# defender.net
KiCad netlist of a schematic drawn in EAGLE
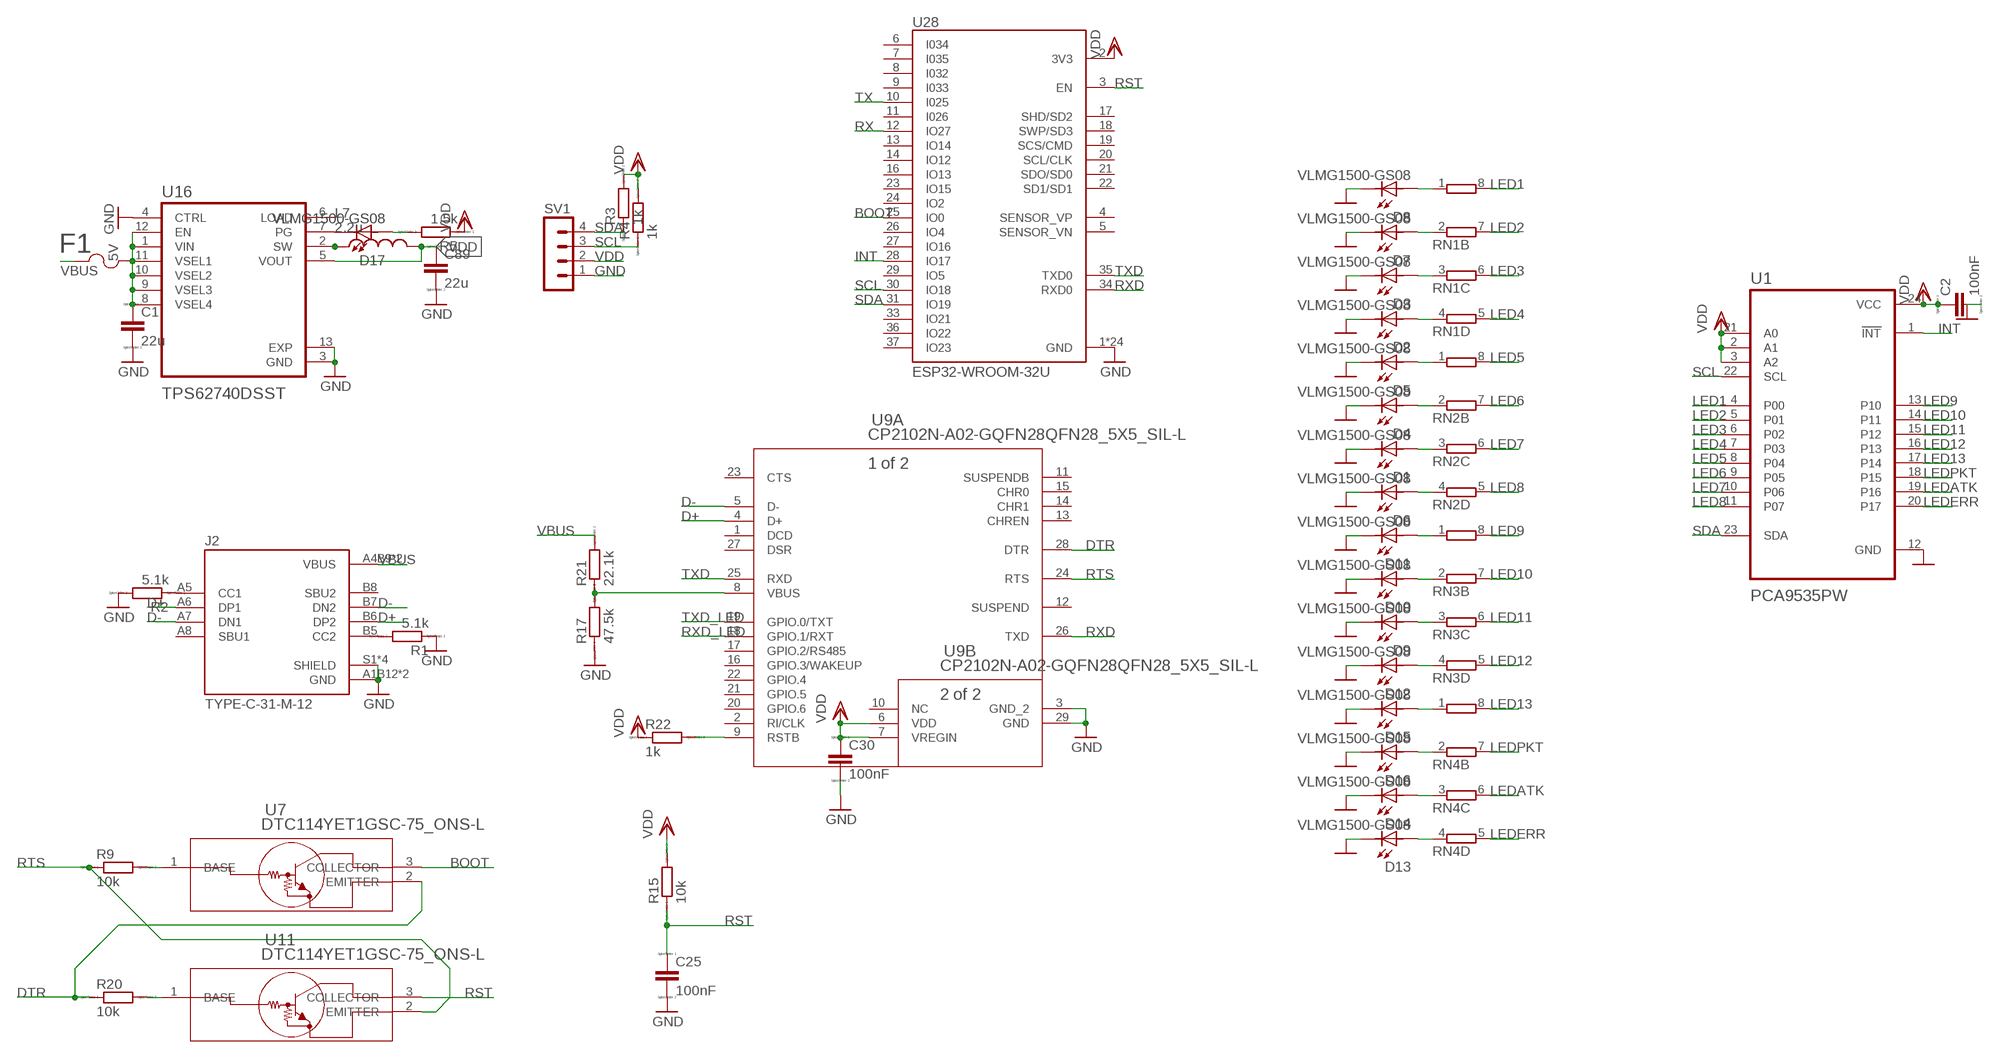
[diagram p0: schematic, sheet 1]

(export (version "E")
  (design (tool "Eeschema 10.0.6"))
  (components
    (comp (ref "C1")
      (value "22u")
      (footprint "eagle-import:C0603R")
      (libsource (lib "eagle-import") (part "CC0603R"))
    )
    (comp (ref "C2")
      (value "100nF")
      (footprint "eagle-import:C0402")
      (libsource (lib "eagle-import") (part "CC0402"))
    )
    (comp (ref "C25")
      (value "100nF")
      (footprint "eagle-import:C0402")
      (libsource (lib "eagle-import") (part "CC0402"))
    )
    (comp (ref "C30")
      (value "100nF")
      (footprint "eagle-import:C0402")
      (libsource (lib "eagle-import") (part "CC0402"))
    )
    (comp (ref "C89")
      (value "22u")
      (footprint "eagle-import:C0603R")
      (libsource (lib "eagle-import") (part "CC0603R"))
    )
    (comp (ref "D1")
      (value "VLMG1500-GS08")
      (footprint "eagle-import:LEDC1005X35N")
      (fields (field (name "MF") "Vishay"))
      (libsource (lib "eagle-import") (part "VLMG1500-GS08"))
    )
    (comp (ref "D2")
      (value "VLMG1500-GS08")
      (footprint "eagle-import:LEDC1005X35N")
      (fields (field (name "MF") "Vishay"))
      (libsource (lib "eagle-import") (part "VLMG1500-GS08"))
    )
    (comp (ref "D3")
      (value "VLMG1500-GS08")
      (footprint "eagle-import:LEDC1005X35N")
      (fields (field (name "MF") "Vishay"))
      (libsource (lib "eagle-import") (part "VLMG1500-GS08"))
    )
    (comp (ref "D4")
      (value "VLMG1500-GS08")
      (footprint "eagle-import:LEDC1005X35N")
      (fields (field (name "MF") "Vishay"))
      (libsource (lib "eagle-import") (part "VLMG1500-GS08"))
    )
    (comp (ref "D5")
      (value "VLMG1500-GS08")
      (footprint "eagle-import:LEDC1005X35N")
      (fields (field (name "MF") "Vishay"))
      (libsource (lib "eagle-import") (part "VLMG1500-GS08"))
    )
    (comp (ref "D6")
      (value "VLMG1500-GS08")
      (footprint "eagle-import:LEDC1005X35N")
      (fields (field (name "MF") "Vishay"))
      (libsource (lib "eagle-import") (part "VLMG1500-GS08"))
    )
    (comp (ref "D7")
      (value "VLMG1500-GS08")
      (footprint "eagle-import:LEDC1005X35N")
      (fields (field (name "MF") "Vishay"))
      (libsource (lib "eagle-import") (part "VLMG1500-GS08"))
    )
    (comp (ref "D8")
      (value "VLMG1500-GS08")
      (footprint "eagle-import:LEDC1005X35N")
      (fields (field (name "MF") "Vishay"))
      (libsource (lib "eagle-import") (part "VLMG1500-GS08"))
    )
    (comp (ref "D9")
      (value "VLMG1500-GS08")
      (footprint "eagle-import:LEDC1005X35N")
      (fields (field (name "MF") "Vishay"))
      (libsource (lib "eagle-import") (part "VLMG1500-GS08"))
    )
    (comp (ref "D10")
      (value "VLMG1500-GS08")
      (footprint "eagle-import:LEDC1005X35N")
      (fields (field (name "MF") "Vishay"))
      (libsource (lib "eagle-import") (part "VLMG1500-GS08"))
    )
    (comp (ref "D11")
      (value "VLMG1500-GS08")
      (footprint "eagle-import:LEDC1005X35N")
      (fields (field (name "MF") "Vishay"))
      (libsource (lib "eagle-import") (part "VLMG1500-GS08"))
    )
    (comp (ref "D12")
      (value "VLMG1500-GS08")
      (footprint "eagle-import:LEDC1005X35N")
      (fields (field (name "MF") "Vishay"))
      (libsource (lib "eagle-import") (part "VLMG1500-GS08"))
    )
    (comp (ref "D13")
      (value "VLMG1500-GS08")
      (footprint "eagle-import:LEDC1005X35N")
      (fields (field (name "MF") "Vishay"))
      (libsource (lib "eagle-import") (part "VLMG1500-GS08"))
    )
    (comp (ref "D14")
      (value "VLMG1500-GS08")
      (footprint "eagle-import:LEDC1005X35N")
      (fields (field (name "MF") "Vishay"))
      (libsource (lib "eagle-import") (part "VLMG1500-GS08"))
    )
    (comp (ref "D15")
      (value "VLMG1500-GS08")
      (footprint "eagle-import:LEDC1005X35N")
      (fields (field (name "MF") "Vishay"))
      (libsource (lib "eagle-import") (part "VLMG1500-GS08"))
    )
    (comp (ref "D16")
      (value "VLMG1500-GS08")
      (footprint "eagle-import:LEDC1005X35N")
      (fields (field (name "MF") "Vishay"))
      (libsource (lib "eagle-import") (part "VLMG1500-GS08"))
    )
    (comp (ref "D17")
      (value "VLMG1500-GS08")
      (footprint "eagle-import:LEDC1005X35N")
      (fields (field (name "MF") "Vishay"))
      (libsource (lib "eagle-import") (part "VLMG1500-GS08"))
    )
    (comp (ref "F1")
      (value "1210L050YR1210LSERIES_LTF-L")
      (footprint "eagle-import:1210LSERIES_LTF-L")
      (fields (field (name "MANUFACTURER_PART_NUMBER") "1210L050YR"))
      (libsource (lib "eagle-import") (part "1210L050YR1210LSERIES_LTF-L"))
    )
    (comp (ref "J2")
      (value "TYPE-C-31-M-12")
      (footprint "eagle-import:HRO_TYPE-C-31-M-12")
      (fields (field (name "MF") "HRO Electronics Co., Ltd."))
      (libsource (lib "eagle-import") (part "TYPE-C-31-M-12"))
    )
    (comp (ref "L7")
      (value "2.2u")
      (footprint "eagle-import:INDC3225X120N")
      (fields (field (name "MF") "Murata") (field (name "MP") "1277AS-H-1R5M=P2"))
      (libsource (lib "eagle-import") (part "1277AS-H-1R5M=P2"))
    )
    (comp (ref "R1")
      (value "5.1k")
      (footprint "eagle-import:R0402")
      (libsource (lib "eagle-import") (part "RR0402"))
    )
    (comp (ref "R2")
      (value "5.1k")
      (footprint "eagle-import:R0402")
      (libsource (lib "eagle-import") (part "RR0402"))
    )
    (comp (ref "R3")
      (value "1k")
      (footprint "eagle-import:R0402")
      (libsource (lib "eagle-import") (part "RR0402"))
    )
    (comp (ref "R4")
      (value "1k")
      (footprint "eagle-import:R0402")
      (libsource (lib "eagle-import") (part "RR0402"))
    )
    (comp (ref "R5")
      (value "1.5k")
      (footprint "eagle-import:R0402")
      (libsource (lib "eagle-import") (part "RR0402"))
    )
    (comp (ref "R9")
      (value "10k")
      (footprint "eagle-import:R0402")
      (libsource (lib "eagle-import") (part "RR0402"))
    )
    (comp (ref "R15")
      (value "10k")
      (footprint "eagle-import:R0402")
      (libsource (lib "eagle-import") (part "RR0402"))
    )
    (comp (ref "R17")
      (value "47.5k")
      (footprint "eagle-import:R0402")
      (libsource (lib "eagle-import") (part "RR0402"))
    )
    (comp (ref "R20")
      (value "10k")
      (footprint "eagle-import:R0402")
      (libsource (lib "eagle-import") (part "RR0402"))
    )
    (comp (ref "R21")
      (value "22.1k")
      (footprint "eagle-import:R0402")
      (libsource (lib "eagle-import") (part "RR0402"))
    )
    (comp (ref "R22")
      (value "1k")
      (footprint "eagle-import:R0402")
      (libsource (lib "eagle-import") (part "RR0402"))
    )
    (comp (ref "RN1")
      (value "4R-N0402ARV341")
      (footprint "eagle-import:4X0402ARV341")
      (libsource (lib "eagle-import") (part "4R-N0402ARV341"))
    )
    (comp (ref "RN2")
      (value "4R-N0402ARV341")
      (footprint "eagle-import:4X0402ARV341")
      (libsource (lib "eagle-import") (part "4R-N0402ARV341"))
    )
    (comp (ref "RN3")
      (value "4R-N0402ARV341")
      (footprint "eagle-import:4X0402ARV341")
      (libsource (lib "eagle-import") (part "4R-N0402ARV341"))
    )
    (comp (ref "RN4")
      (value "4R-N0402ARV341")
      (footprint "eagle-import:4X0402ARV341")
      (libsource (lib "eagle-import") (part "4R-N0402ARV341"))
    )
    (comp (ref "SV1")
      (value "MA04-1")
      (footprint "eagle-import:MA04-1")
      (libsource (lib "eagle-import") (part "MA04-1"))
    )
    (comp (ref "U1")
      (value "PCA9535PW")
      (footprint "eagle-import:SOP65P640X120-24N")
      (fields (field (name "MF") "Texas Instruments"))
      (libsource (lib "eagle-import") (part "PCA9535PW"))
    )
    (comp (ref "U7")
      (value "DTC114YET1GSC-75_ONS-L")
      (footprint "eagle-import:SC-75_ONS-L")
      (fields
        (field (name "MANUFACTURER_PART_NUMBER") "DTC114YET1G")
        (field (name "COPYRIGHT") "Copyright (C) 2018 Accelerated Designs. All rights reserved")
      )
      (libsource (lib "eagle-import") (part "DTC114YET1GSC-75_ONS-L"))
    )
    (comp (ref "U9")
      (value "CP2102N-A02-GQFN28QFN28_5X5_SIL-L")
      (footprint "eagle-import:QFN28_5X5_SIL-L")
      (fields
        (field (name "MANUFACTURER_PART_NUMBER") "CP2102N-A02-GQFN28")
        (field (name "COPYRIGHT") "Copyright (C) 2018 Accelerated Designs. All rights reserved")
      )
      (libsource (lib "eagle-import") (part "CP2102N-A02-GQFN28QFN28_5X5_SIL-L"))
    )
    (comp (ref "U11")
      (value "DTC114YET1GSC-75_ONS-L")
      (footprint "eagle-import:SC-75_ONS-L")
      (fields
        (field (name "MANUFACTURER_PART_NUMBER") "DTC114YET1G")
        (field (name "COPYRIGHT") "Copyright (C) 2018 Accelerated Designs. All rights reserved")
      )
      (libsource (lib "eagle-import") (part "DTC114YET1GSC-75_ONS-L"))
    )
    (comp (ref "U16")
      (value "TPS62740DSST")
      (footprint "eagle-import:VREG_LM27762DSSR")
      (fields (field (name "MF") "Texas Instruments") (field (name "MP") "TPS62740DSS"))
      (libsource (lib "eagle-import") (part "TPS62740DSST"))
    )
    (comp (ref "U28")
      (value "ESP32-WROOM-32U")
      (footprint "eagle-import:XCVR_ESP32-WROOM-32U")
      (fields (field (name "MF") "Espressif Systems"))
      (libsource (lib "eagle-import") (part "ESP32-WROOM-32U"))
    )
  )
  (nets
    (net (code "1") (name "/5V") (class "Default")
      (node (ref "C1") (pin "1") (pinfunction "1_1") (pintype "passive"))
      (node (ref "F1") (pin "2") (pinfunction "2_2") (pintype "passive"))
      (node (ref "U16") (pin "1") (pinfunction "VIN_1") (pintype "input"))
      (node (ref "U16") (pin "10") (pinfunction "VSEL2_10") (pintype "input"))
      (node (ref "U16") (pin "11") (pinfunction "VSEL1_11") (pintype "input"))
      (node (ref "U16") (pin "12") (pinfunction "EN_12") (pintype "input"))
      (node (ref "U16") (pin "8") (pinfunction "VSEL4_8") (pintype "input"))
      (node (ref "U16") (pin "9") (pinfunction "VSEL3_9") (pintype "input"))
    )
    (net (code "2") (name "/BOOT") (class "Default")
      (node (ref "U28") (pin "25") (pinfunction "IO0_25") (pintype "bidirectional"))
      (node (ref "U7") (pin "3") (pinfunction "COLLECTOR_3") (pintype "output"))
    )
    (net (code "3") (name "/D+") (class "Default")
      (node (ref "J2") (pin "A6") (pinfunction "DP1_A6") (pintype "bidirectional"))
      (node (ref "J2") (pin "B6") (pinfunction "DP2_B6") (pintype "bidirectional"))
      (node (ref "U9") (pin "4") (pinfunction "D+_4") (pintype "input"))
    )
    (net (code "4") (name "/D-") (class "Default")
      (node (ref "J2") (pin "A7") (pinfunction "DN1_A7") (pintype "bidirectional"))
      (node (ref "J2") (pin "B7") (pinfunction "DN2_B7") (pintype "bidirectional"))
      (node (ref "U9") (pin "5") (pinfunction "D-_5") (pintype "input"))
    )
    (net (code "5") (name "/DTR") (class "Default")
      (node (ref "R20") (pin "1") (pinfunction "1_1") (pintype "passive"))
      (node (ref "U7") (pin "2") (pinfunction "EMITTER_2") (pintype "passive"))
      (node (ref "U9") (pin "28") (pinfunction "DTR_28") (pintype "output"))
    )
    (net (code "6") (name "/INT") (class "Default")
      (node (ref "U1") (pin "1") (pinfunction "~{INT}_1") (pintype "output"))
      (node (ref "U28") (pin "28") (pinfunction "IO17_28") (pintype "bidirectional"))
    )
    (net (code "7") (name "/LED1") (class "Default")
      (node (ref "RN1") (pin "8") (pinfunction "2_8") (pintype "passive"))
      (node (ref "U1") (pin "4") (pinfunction "P00_4") (pintype "bidirectional"))
    )
    (net (code "8") (name "/LED2") (class "Default")
      (node (ref "RN1") (pin "7") (pinfunction "2_7") (pintype "passive"))
      (node (ref "U1") (pin "5") (pinfunction "P01_5") (pintype "bidirectional"))
    )
    (net (code "9") (name "/LED3") (class "Default")
      (node (ref "RN1") (pin "6") (pinfunction "2_6") (pintype "passive"))
      (node (ref "U1") (pin "6") (pinfunction "P02_6") (pintype "bidirectional"))
    )
    (net (code "10") (name "/LED4") (class "Default")
      (node (ref "RN1") (pin "5") (pinfunction "2_5") (pintype "passive"))
      (node (ref "U1") (pin "7") (pinfunction "P03_7") (pintype "bidirectional"))
    )
    (net (code "11") (name "/LED5") (class "Default")
      (node (ref "RN2") (pin "8") (pinfunction "2_8") (pintype "passive"))
      (node (ref "U1") (pin "8") (pinfunction "P04_8") (pintype "bidirectional"))
    )
    (net (code "12") (name "/LED6") (class "Default")
      (node (ref "RN2") (pin "7") (pinfunction "2_7") (pintype "passive"))
      (node (ref "U1") (pin "9") (pinfunction "P05_9") (pintype "bidirectional"))
    )
    (net (code "13") (name "/LED7") (class "Default")
      (node (ref "RN2") (pin "6") (pinfunction "2_6") (pintype "passive"))
      (node (ref "U1") (pin "10") (pinfunction "P06_10") (pintype "bidirectional"))
    )
    (net (code "14") (name "/LED8") (class "Default")
      (node (ref "RN2") (pin "5") (pinfunction "2_5") (pintype "passive"))
      (node (ref "U1") (pin "11") (pinfunction "P07_11") (pintype "bidirectional"))
    )
    (net (code "15") (name "/LED9") (class "Default")
      (node (ref "RN3") (pin "8") (pinfunction "2_8") (pintype "passive"))
      (node (ref "U1") (pin "13") (pinfunction "P10_13") (pintype "bidirectional"))
    )
    (net (code "16") (name "/LED10") (class "Default")
      (node (ref "RN3") (pin "7") (pinfunction "2_7") (pintype "passive"))
      (node (ref "U1") (pin "14") (pinfunction "P11_14") (pintype "bidirectional"))
    )
    (net (code "17") (name "/LED11") (class "Default")
      (node (ref "RN3") (pin "6") (pinfunction "2_6") (pintype "passive"))
      (node (ref "U1") (pin "15") (pinfunction "P12_15") (pintype "bidirectional"))
    )
    (net (code "18") (name "/LED12") (class "Default")
      (node (ref "RN3") (pin "5") (pinfunction "2_5") (pintype "passive"))
      (node (ref "U1") (pin "16") (pinfunction "P13_16") (pintype "bidirectional"))
    )
    (net (code "19") (name "/LED13") (class "Default")
      (node (ref "RN4") (pin "8") (pinfunction "2_8") (pintype "passive"))
      (node (ref "U1") (pin "17") (pinfunction "P14_17") (pintype "bidirectional"))
    )
    (net (code "20") (name "/LEDATK") (class "Default")
      (node (ref "RN4") (pin "6") (pinfunction "2_6") (pintype "passive"))
      (node (ref "U1") (pin "19") (pinfunction "P16_19") (pintype "bidirectional"))
    )
    (net (code "21") (name "/LEDERR") (class "Default")
      (node (ref "RN4") (pin "5") (pinfunction "2_5") (pintype "passive"))
      (node (ref "U1") (pin "20") (pinfunction "P17_20") (pintype "bidirectional"))
    )
    (net (code "22") (name "/LEDPKT") (class "Default")
      (node (ref "RN4") (pin "7") (pinfunction "2_7") (pintype "passive"))
      (node (ref "U1") (pin "18") (pinfunction "P15_18") (pintype "bidirectional"))
    )
    (net (code "23") (name "/RST") (class "Default")
      (node (ref "C25") (pin "1") (pinfunction "1_1") (pintype "passive"))
      (node (ref "R15") (pin "1") (pinfunction "1_1") (pintype "passive"))
      (node (ref "U11") (pin "3") (pinfunction "COLLECTOR_3") (pintype "output"))
      (node (ref "U28") (pin "3") (pinfunction "EN_3") (pintype "input"))
    )
    (net (code "24") (name "/RTS") (class "Default")
      (node (ref "R9") (pin "1") (pinfunction "1_1") (pintype "passive"))
      (node (ref "U11") (pin "2") (pinfunction "EMITTER_2") (pintype "passive"))
      (node (ref "U9") (pin "24") (pinfunction "RTS_24") (pintype "output"))
    )
    (net (code "25") (name "/RX") (class "Default")
      (node (ref "U28") (pin "12") (pinfunction "IO27_12") (pintype "bidirectional"))
    )
    (net (code "26") (name "/RXD") (class "Default")
      (node (ref "U28") (pin "34") (pinfunction "RXD0_34") (pintype "bidirectional"))
      (node (ref "U9") (pin "26") (pinfunction "TXD_26") (pintype "output"))
    )
    (net (code "27") (name "/RXD_LED") (class "Default")
      (node (ref "U9") (pin "18") (pinfunction "GPIO.1/RXT_18") (pintype "bidirectional"))
    )
    (net (code "28") (name "/SCL") (class "Default")
      (node (ref "R4") (pin "1") (pinfunction "1_1") (pintype "passive"))
      (node (ref "SV1") (pin "3") (pinfunction "3_3") (pintype "passive"))
      (node (ref "U1") (pin "22") (pinfunction "SCL_22") (pintype "input"))
      (node (ref "U28") (pin "30") (pinfunction "IO18_30") (pintype "bidirectional"))
    )
    (net (code "29") (name "/SDA") (class "Default")
      (node (ref "R3") (pin "1") (pinfunction "1_1") (pintype "passive"))
      (node (ref "SV1") (pin "4") (pinfunction "4_4") (pintype "passive"))
      (node (ref "U1") (pin "23") (pinfunction "SDA_23") (pintype "bidirectional"))
      (node (ref "U28") (pin "31") (pinfunction "IO19_31") (pintype "bidirectional"))
    )
    (net (code "30") (name "/TX") (class "Default")
      (node (ref "U28") (pin "10") (pinfunction "I025_10") (pintype "bidirectional"))
    )
    (net (code "31") (name "/TXD") (class "Default")
      (node (ref "U28") (pin "35") (pinfunction "TXD0_35") (pintype "bidirectional"))
      (node (ref "U9") (pin "25") (pinfunction "RXD_25") (pintype "input"))
    )
    (net (code "32") (name "/TXD_LED") (class "Default")
      (node (ref "U9") (pin "19") (pinfunction "GPIO.0/TXT_19") (pintype "bidirectional"))
    )
    (net (code "33") (name "/VBUS") (class "Default")
      (node (ref "F1") (pin "1") (pinfunction "1_1") (pintype "passive"))
      (node (ref "J2") (pin "A4B9") (pinfunction "VBUS_A4B9") (pintype "power_in"))
      (node (ref "J2") (pin "B4A9") (pinfunction "VBUS_B4A9") (pintype "power_in"))
      (node (ref "R21") (pin "2") (pinfunction "2_2") (pintype "passive"))
    )
    (net (code "34") (name "GND") (class "Default")
      (node (ref "C1") (pin "2") (pinfunction "2_2") (pintype "passive"))
      (node (ref "C2") (pin "2") (pinfunction "2_2") (pintype "passive"))
      (node (ref "C25") (pin "2") (pinfunction "2_2") (pintype "passive"))
      (node (ref "C30") (pin "2") (pinfunction "2_2") (pintype "passive"))
      (node (ref "C89") (pin "2") (pinfunction "2_2") (pintype "passive"))
      (node (ref "D1") (pin "2") (pinfunction "2_2") (pintype "passive"))
      (node (ref "D10") (pin "2") (pinfunction "2_2") (pintype "passive"))
      (node (ref "D11") (pin "2") (pinfunction "2_2") (pintype "passive"))
      (node (ref "D12") (pin "2") (pinfunction "2_2") (pintype "passive"))
      (node (ref "D13") (pin "2") (pinfunction "2_2") (pintype "passive"))
      (node (ref "D14") (pin "2") (pinfunction "2_2") (pintype "passive"))
      (node (ref "D15") (pin "2") (pinfunction "2_2") (pintype "passive"))
      (node (ref "D16") (pin "2") (pinfunction "2_2") (pintype "passive"))
      (node (ref "D2") (pin "2") (pinfunction "2_2") (pintype "passive"))
      (node (ref "D3") (pin "2") (pinfunction "2_2") (pintype "passive"))
      (node (ref "D4") (pin "2") (pinfunction "2_2") (pintype "passive"))
      (node (ref "D5") (pin "2") (pinfunction "2_2") (pintype "passive"))
      (node (ref "D6") (pin "2") (pinfunction "2_2") (pintype "passive"))
      (node (ref "D7") (pin "2") (pinfunction "2_2") (pintype "passive"))
      (node (ref "D8") (pin "2") (pinfunction "2_2") (pintype "passive"))
      (node (ref "D9") (pin "2") (pinfunction "2_2") (pintype "passive"))
      (node (ref "J2") (pin "A1B12") (pinfunction "GND_A1B12") (pintype "power_in"))
      (node (ref "J2") (pin "B1A12") (pinfunction "GND_B1A12") (pintype "power_in"))
      (node (ref "J2") (pin "S1") (pinfunction "SHIELD_S1") (pintype "passive"))
      (node (ref "J2") (pin "S2") (pinfunction "SHIELD_S2") (pintype "passive"))
      (node (ref "J2") (pin "S3") (pinfunction "SHIELD_S3") (pintype "passive"))
      (node (ref "J2") (pin "S4") (pinfunction "SHIELD_S4") (pintype "passive"))
      (node (ref "R1") (pin "1") (pinfunction "1_1") (pintype "passive"))
      (node (ref "R17") (pin "1") (pinfunction "1_1") (pintype "passive"))
      (node (ref "R2") (pin "2") (pinfunction "2_2") (pintype "passive"))
      (node (ref "SV1") (pin "1") (pinfunction "1_1") (pintype "passive"))
      (node (ref "U1") (pin "12") (pinfunction "GND_12") (pintype "power_in"))
      (node (ref "U16") (pin "13") (pinfunction "EXP_13") (pintype "power_in"))
      (node (ref "U16") (pin "3") (pinfunction "GND_3") (pintype "power_in"))
      (node (ref "U16") (pin "4") (pinfunction "CTRL_4") (pintype "input"))
      (node (ref "U28") (pin "1") (pinfunction "GND_1") (pintype "power_in"))
      (node (ref "U28") (pin "15") (pinfunction "GND_15") (pintype "power_in"))
      (node (ref "U28") (pin "38") (pinfunction "GND_38") (pintype "power_in"))
      (node (ref "U28") (pin "G.1") (pinfunction "GND_G.1") (pintype "power_in"))
      (node (ref "U28") (pin "G.10") (pinfunction "GND_G.10") (pintype "power_in"))
      (node (ref "U28") (pin "G.11") (pinfunction "GND_G.11") (pintype "power_in"))
      (node (ref "U28") (pin "G.12") (pinfunction "GND_G.12") (pintype "power_in"))
      (node (ref "U28") (pin "G.13") (pinfunction "GND_G.13") (pintype "power_in"))
      (node (ref "U28") (pin "G.14") (pinfunction "GND_G.14") (pintype "power_in"))
      (node (ref "U28") (pin "G.15") (pinfunction "GND_G.15") (pintype "power_in"))
      (node (ref "U28") (pin "G.16") (pinfunction "GND_G.16") (pintype "power_in"))
      (node (ref "U28") (pin "G.17") (pinfunction "GND_G.17") (pintype "power_in"))
      (node (ref "U28") (pin "G.18") (pinfunction "GND_G.18") (pintype "power_in"))
      (node (ref "U28") (pin "G.19") (pinfunction "GND_G.19") (pintype "power_in"))
      (node (ref "U28") (pin "G.2") (pinfunction "GND_G.2") (pintype "power_in"))
      (node (ref "U28") (pin "G.20") (pinfunction "GND_G.20") (pintype "power_in"))
      (node (ref "U28") (pin "G.21") (pinfunction "GND_G.21") (pintype "power_in"))
      (node (ref "U28") (pin "G.22") (pinfunction "GND_G.22") (pintype "power_in"))
      (node (ref "U28") (pin "G.4") (pinfunction "GND_G.4") (pintype "power_in"))
      (node (ref "U28") (pin "G.5") (pinfunction "GND_G.5") (pintype "power_in"))
      (node (ref "U28") (pin "G.6") (pinfunction "GND_G.6") (pintype "power_in"))
      (node (ref "U28") (pin "G.7") (pinfunction "GND_G.7") (pintype "power_in"))
      (node (ref "U28") (pin "G.8") (pinfunction "GND_G.8") (pintype "power_in"))
      (node (ref "U28") (pin "G.9") (pinfunction "GND_G.9") (pintype "power_in"))
      (node (ref "U9") (pin "29") (pinfunction "GND_29") (pintype "passive"))
      (node (ref "U9") (pin "3") (pinfunction "GND_2_3") (pintype "passive"))
    )
    (net (code "35") (name "Net-(D5-Pad1)") (class "Default")
      (node (ref "D5") (pin "1") (pinfunction "1_1") (pintype "passive"))
      (node (ref "RN2") (pin "1") (pinfunction "1_1") (pintype "passive"))
    )
    (net (code "36") (name "Net-(D8-Pad1)") (class "Default")
      (node (ref "D8") (pin "1") (pinfunction "1_1") (pintype "passive"))
      (node (ref "RN1") (pin "1") (pinfunction "1_1") (pintype "passive"))
    )
    (net (code "37") (name "Net-(D11-Pad1)") (class "Default")
      (node (ref "D11") (pin "1") (pinfunction "1_1") (pintype "passive"))
      (node (ref "RN3") (pin "1") (pinfunction "1_1") (pintype "passive"))
    )
    (net (code "38") (name "Net-(D15-Pad1)") (class "Default")
      (node (ref "D15") (pin "1") (pinfunction "1_1") (pintype "passive"))
      (node (ref "RN4") (pin "1") (pinfunction "1_1") (pintype "passive"))
    )
    (net (code "39") (name "Net-(D17-Pad1)") (class "Default")
      (node (ref "D17") (pin "1") (pinfunction "1_1") (pintype "passive"))
      (node (ref "R5") (pin "2") (pinfunction "2_2") (pintype "passive"))
    )
    (net (code "40") (name "Net-(J2-CC1)") (class "Default")
      (node (ref "J2") (pin "A5") (pinfunction "CC1_A5") (pintype "bidirectional"))
      (node (ref "R2") (pin "1") (pinfunction "1_1") (pintype "passive"))
    )
    (net (code "41") (name "Net-(J2-CC2)") (class "Default")
      (node (ref "J2") (pin "B5") (pinfunction "CC2_B5") (pintype "bidirectional"))
      (node (ref "R1") (pin "2") (pinfunction "2_2") (pintype "passive"))
    )
    (net (code "42") (name "Net-(RN1B-1)") (class "Default")
      (node (ref "D7") (pin "1") (pinfunction "1_1") (pintype "passive"))
      (node (ref "RN1") (pin "2") (pinfunction "1_2") (pintype "passive"))
    )
    (net (code "43") (name "Net-(RN1C-1)") (class "Default")
      (node (ref "D3") (pin "1") (pinfunction "1_1") (pintype "passive"))
      (node (ref "RN1") (pin "3") (pinfunction "1_3") (pintype "passive"))
    )
    (net (code "44") (name "Net-(RN1D-1)") (class "Default")
      (node (ref "D2") (pin "1") (pinfunction "1_1") (pintype "passive"))
      (node (ref "RN1") (pin "4") (pinfunction "1_4") (pintype "passive"))
    )
    (net (code "45") (name "Net-(RN2B-1)") (class "Default")
      (node (ref "D4") (pin "1") (pinfunction "1_1") (pintype "passive"))
      (node (ref "RN2") (pin "2") (pinfunction "1_2") (pintype "passive"))
    )
    (net (code "46") (name "Net-(RN2C-1)") (class "Default")
      (node (ref "D1") (pin "1") (pinfunction "1_1") (pintype "passive"))
      (node (ref "RN2") (pin "3") (pinfunction "1_3") (pintype "passive"))
    )
    (net (code "47") (name "Net-(RN2D-1)") (class "Default")
      (node (ref "D6") (pin "1") (pinfunction "1_1") (pintype "passive"))
      (node (ref "RN2") (pin "4") (pinfunction "1_4") (pintype "passive"))
    )
    (net (code "48") (name "Net-(RN3B-1)") (class "Default")
      (node (ref "D10") (pin "1") (pinfunction "1_1") (pintype "passive"))
      (node (ref "RN3") (pin "2") (pinfunction "1_2") (pintype "passive"))
    )
    (net (code "49") (name "Net-(RN3C-1)") (class "Default")
      (node (ref "D9") (pin "1") (pinfunction "1_1") (pintype "passive"))
      (node (ref "RN3") (pin "3") (pinfunction "1_3") (pintype "passive"))
    )
    (net (code "50") (name "Net-(RN3D-1)") (class "Default")
      (node (ref "D12") (pin "1") (pinfunction "1_1") (pintype "passive"))
      (node (ref "RN3") (pin "4") (pinfunction "1_4") (pintype "passive"))
    )
    (net (code "51") (name "Net-(RN4B-1)") (class "Default")
      (node (ref "D16") (pin "1") (pinfunction "1_1") (pintype "passive"))
      (node (ref "RN4") (pin "2") (pinfunction "1_2") (pintype "passive"))
    )
    (net (code "52") (name "Net-(RN4C-1)") (class "Default")
      (node (ref "D14") (pin "1") (pinfunction "1_1") (pintype "passive"))
      (node (ref "RN4") (pin "3") (pinfunction "1_3") (pintype "passive"))
    )
    (net (code "53") (name "Net-(RN4D-1)") (class "Default")
      (node (ref "D13") (pin "1") (pinfunction "1_1") (pintype "passive"))
      (node (ref "RN4") (pin "4") (pinfunction "1_4") (pintype "passive"))
    )
    (net (code "54") (name "Net-(U7-BASE)") (class "Default")
      (node (ref "R9") (pin "2") (pinfunction "2_2") (pintype "passive"))
      (node (ref "U7") (pin "1") (pinfunction "BASE_1") (pintype "input"))
    )
    (net (code "55") (name "Net-(U9A-RSTB)") (class "Default")
      (node (ref "R22") (pin "2") (pinfunction "2_2") (pintype "passive"))
      (node (ref "U9") (pin "9") (pinfunction "RSTB_9") (pintype "passive"))
    )
    (net (code "56") (name "Net-(U9A-VBUS)") (class "Default")
      (node (ref "R17") (pin "2") (pinfunction "2_2") (pintype "passive"))
      (node (ref "R21") (pin "1") (pinfunction "1_1") (pintype "passive"))
      (node (ref "U9") (pin "8") (pinfunction "VBUS_8") (pintype "input"))
    )
    (net (code "57") (name "Net-(U11-BASE)") (class "Default")
      (node (ref "R20") (pin "2") (pinfunction "2_2") (pintype "passive"))
      (node (ref "U11") (pin "1") (pinfunction "BASE_1") (pintype "input"))
    )
    (net (code "58") (name "Net-(U16-PG)") (class "Default")
      (node (ref "D17") (pin "2") (pinfunction "2_2") (pintype "passive"))
      (node (ref "U16") (pin "7") (pinfunction "PG_7") (pintype "output"))
    )
    (net (code "59") (name "Net-(U16-SW)") (class "Default")
      (node (ref "L7") (pin "1") (pinfunction "1_1") (pintype "passive"))
      (node (ref "U16") (pin "2") (pinfunction "SW_2") (pintype "output"))
    )
    (net (code "60") (name "VDD") (class "Default")
      (node (ref "C2") (pin "1") (pinfunction "1_1") (pintype "passive"))
      (node (ref "C30") (pin "1") (pinfunction "1_1") (pintype "passive"))
      (node (ref "C89") (pin "1") (pinfunction "1_1") (pintype "passive"))
      (node (ref "L7") (pin "2") (pinfunction "2_2") (pintype "passive"))
      (node (ref "R15") (pin "2") (pinfunction "2_2") (pintype "passive"))
      (node (ref "R22") (pin "1") (pinfunction "1_1") (pintype "passive"))
      (node (ref "R3") (pin "2") (pinfunction "2_2") (pintype "passive"))
      (node (ref "R4") (pin "2") (pinfunction "2_2") (pintype "passive"))
      (node (ref "R5") (pin "1") (pinfunction "1_1") (pintype "passive"))
      (node (ref "SV1") (pin "2") (pinfunction "2_2") (pintype "passive"))
      (node (ref "U1") (pin "2") (pinfunction "A1_2") (pintype "input"))
      (node (ref "U1") (pin "21") (pinfunction "A0_21") (pintype "input"))
      (node (ref "U1") (pin "24") (pinfunction "VCC_24") (pintype "power_in"))
      (node (ref "U1") (pin "3") (pinfunction "A2_3") (pintype "input"))
      (node (ref "U16") (pin "5") (pinfunction "VOUT_5") (pintype "output"))
      (node (ref "U28") (pin "2") (pinfunction "3V3_2") (pintype "power_in"))
      (node (ref "U9") (pin "6") (pinfunction "VDD_6") (pintype "power_in"))
      (node (ref "U9") (pin "7") (pinfunction "VREGIN_7") (pintype "power_in"))
    )
    (net (code "61") (name "unconnected-(J2-SBU1-PadA8)") (class "Default")
      (node (ref "J2") (pin "A8") (pinfunction "SBU1_A8") (pintype "bidirectional"))
    )
    (net (code "62") (name "unconnected-(J2-SBU2-PadB8)") (class "Default")
      (node (ref "J2") (pin "B8") (pinfunction "SBU2_B8") (pintype "bidirectional"))
    )
    (net (code "63") (name "unconnected-(U9A-CHR0-Pad15)") (class "Default")
      (node (ref "U9") (pin "15") (pinfunction "CHR0_15") (pintype "output"))
    )
    (net (code "64") (name "unconnected-(U9A-CHR1-Pad14)") (class "Default")
      (node (ref "U9") (pin "14") (pinfunction "CHR1_14") (pintype "output"))
    )
    (net (code "65") (name "unconnected-(U9A-CHREN-Pad13)") (class "Default")
      (node (ref "U9") (pin "13") (pinfunction "CHREN_13") (pintype "output"))
    )
    (net (code "66") (name "unconnected-(U9A-CTS-Pad23)") (class "Default")
      (node (ref "U9") (pin "23") (pinfunction "CTS_23") (pintype "input"))
    )
    (net (code "67") (name "unconnected-(U9A-DCD-Pad1)") (class "Default")
      (node (ref "U9") (pin "1") (pinfunction "DCD_1") (pintype "input"))
    )
    (net (code "68") (name "unconnected-(U9A-DSR-Pad27)") (class "Default")
      (node (ref "U9") (pin "27") (pinfunction "DSR_27") (pintype "input"))
    )
    (net (code "69") (name "unconnected-(U9A-GPIO.2{slash}RS485-Pad17)") (class "Default")
      (node (ref "U9") (pin "17") (pinfunction "GPIO.2/RS485_17") (pintype "bidirectional"))
    )
    (net (code "70") (name "unconnected-(U9A-GPIO.3{slash}WAKEUP-Pad16)") (class "Default")
      (node (ref "U9") (pin "16") (pinfunction "GPIO.3/WAKEUP_16") (pintype "bidirectional"))
    )
    (net (code "71") (name "unconnected-(U9A-GPIO.4-Pad22)") (class "Default")
      (node (ref "U9") (pin "22") (pinfunction "GPIO.4_22") (pintype "bidirectional"))
    )
    (net (code "72") (name "unconnected-(U9A-GPIO.5-Pad21)") (class "Default")
      (node (ref "U9") (pin "21") (pinfunction "GPIO.5_21") (pintype "bidirectional"))
    )
    (net (code "73") (name "unconnected-(U9A-GPIO.6-Pad20)") (class "Default")
      (node (ref "U9") (pin "20") (pinfunction "GPIO.6_20") (pintype "bidirectional"))
    )
    (net (code "74") (name "unconnected-(U9A-RI{slash}CLK-Pad2)") (class "Default")
      (node (ref "U9") (pin "2") (pinfunction "RI/CLK_2") (pintype "bidirectional"))
    )
    (net (code "75") (name "unconnected-(U9A-SUSPEND-Pad12)") (class "Default")
      (node (ref "U9") (pin "12") (pinfunction "SUSPEND_12") (pintype "output"))
    )
    (net (code "76") (name "unconnected-(U9A-SUSPENDB-Pad11)") (class "Default")
      (node (ref "U9") (pin "11") (pinfunction "SUSPENDB_11") (pintype "output"))
    )
    (net (code "77") (name "unconnected-(U9B-NC-Pad10)") (class "Default")
      (node (ref "U9") (pin "10") (pinfunction "NC_10") (pintype "no_connect"))
    )
    (net (code "78") (name "unconnected-(U16-LOAD-Pad6)") (class "Default")
      (node (ref "U16") (pin "6") (pinfunction "LOAD_6") (pintype "output"))
    )
    (net (code "79") (name "unconnected-(U28-I026-Pad11)") (class "Default")
      (node (ref "U28") (pin "11") (pinfunction "I026_11") (pintype "bidirectional"))
    )
    (net (code "80") (name "unconnected-(U28-I032-Pad8)") (class "Default")
      (node (ref "U28") (pin "8") (pinfunction "I032_8") (pintype "bidirectional"))
    )
    (net (code "81") (name "unconnected-(U28-I033-Pad9)") (class "Default")
      (node (ref "U28") (pin "9") (pinfunction "I033_9") (pintype "bidirectional"))
    )
    (net (code "82") (name "unconnected-(U28-I034-Pad6)") (class "Default")
      (node (ref "U28") (pin "6") (pinfunction "I034_6") (pintype "input"))
    )
    (net (code "83") (name "unconnected-(U28-I035-Pad7)") (class "Default")
      (node (ref "U28") (pin "7") (pinfunction "I035_7") (pintype "input"))
    )
    (net (code "84") (name "unconnected-(U28-IO2-Pad24)") (class "Default")
      (node (ref "U28") (pin "24") (pinfunction "IO2_24") (pintype "bidirectional"))
    )
    (net (code "85") (name "unconnected-(U28-IO4-Pad26)") (class "Default")
      (node (ref "U28") (pin "26") (pinfunction "IO4_26") (pintype "bidirectional"))
    )
    (net (code "86") (name "unconnected-(U28-IO5-Pad29)") (class "Default")
      (node (ref "U28") (pin "29") (pinfunction "IO5_29") (pintype "bidirectional"))
    )
    (net (code "87") (name "unconnected-(U28-IO12-Pad14)") (class "Default")
      (node (ref "U28") (pin "14") (pinfunction "IO12_14") (pintype "bidirectional"))
    )
    (net (code "88") (name "unconnected-(U28-IO13-Pad16)") (class "Default")
      (node (ref "U28") (pin "16") (pinfunction "IO13_16") (pintype "bidirectional"))
    )
    (net (code "89") (name "unconnected-(U28-IO14-Pad13)") (class "Default")
      (node (ref "U28") (pin "13") (pinfunction "IO14_13") (pintype "bidirectional"))
    )
    (net (code "90") (name "unconnected-(U28-IO15-Pad23)") (class "Default")
      (node (ref "U28") (pin "23") (pinfunction "IO15_23") (pintype "bidirectional"))
    )
    (net (code "91") (name "unconnected-(U28-IO16-Pad27)") (class "Default")
      (node (ref "U28") (pin "27") (pinfunction "IO16_27") (pintype "bidirectional"))
    )
    (net (code "92") (name "unconnected-(U28-IO21-Pad33)") (class "Default")
      (node (ref "U28") (pin "33") (pinfunction "IO21_33") (pintype "bidirectional"))
    )
    (net (code "93") (name "unconnected-(U28-IO22-Pad36)") (class "Default")
      (node (ref "U28") (pin "36") (pinfunction "IO22_36") (pintype "bidirectional"))
    )
    (net (code "94") (name "unconnected-(U28-IO23-Pad37)") (class "Default")
      (node (ref "U28") (pin "37") (pinfunction "IO23_37") (pintype "bidirectional"))
    )
    (net (code "95") (name "unconnected-(U28-SCL{slash}CLK-Pad20)") (class "Default")
      (node (ref "U28") (pin "20") (pinfunction "SCL/CLK_20") (pintype "bidirectional"))
    )
    (net (code "96") (name "unconnected-(U28-SCS{slash}CMD-Pad19)") (class "Default")
      (node (ref "U28") (pin "19") (pinfunction "SCS/CMD_19") (pintype "bidirectional"))
    )
    (net (code "97") (name "unconnected-(U28-SD1{slash}SD1-Pad22)") (class "Default")
      (node (ref "U28") (pin "22") (pinfunction "SD1/SD1_22") (pintype "bidirectional"))
    )
    (net (code "98") (name "unconnected-(U28-SDO{slash}SD0-Pad21)") (class "Default")
      (node (ref "U28") (pin "21") (pinfunction "SDO/SD0_21") (pintype "bidirectional"))
    )
    (net (code "99") (name "unconnected-(U28-SENSOR_VN-Pad5)") (class "Default")
      (node (ref "U28") (pin "5") (pinfunction "SENSOR_VN_5") (pintype "input"))
    )
    (net (code "100") (name "unconnected-(U28-SENSOR_VP-Pad4)") (class "Default")
      (node (ref "U28") (pin "4") (pinfunction "SENSOR_VP_4") (pintype "input"))
    )
    (net (code "101") (name "unconnected-(U28-SHD{slash}SD2-Pad17)") (class "Default")
      (node (ref "U28") (pin "17") (pinfunction "SHD/SD2_17") (pintype "bidirectional"))
    )
    (net (code "102") (name "unconnected-(U28-SWP{slash}SD3-Pad18)") (class "Default")
      (node (ref "U28") (pin "18") (pinfunction "SWP/SD3_18") (pintype "bidirectional"))
    )
  )
)
